# Peripherals.net
KiCad netlist of a schematic drawn in Altium Designer
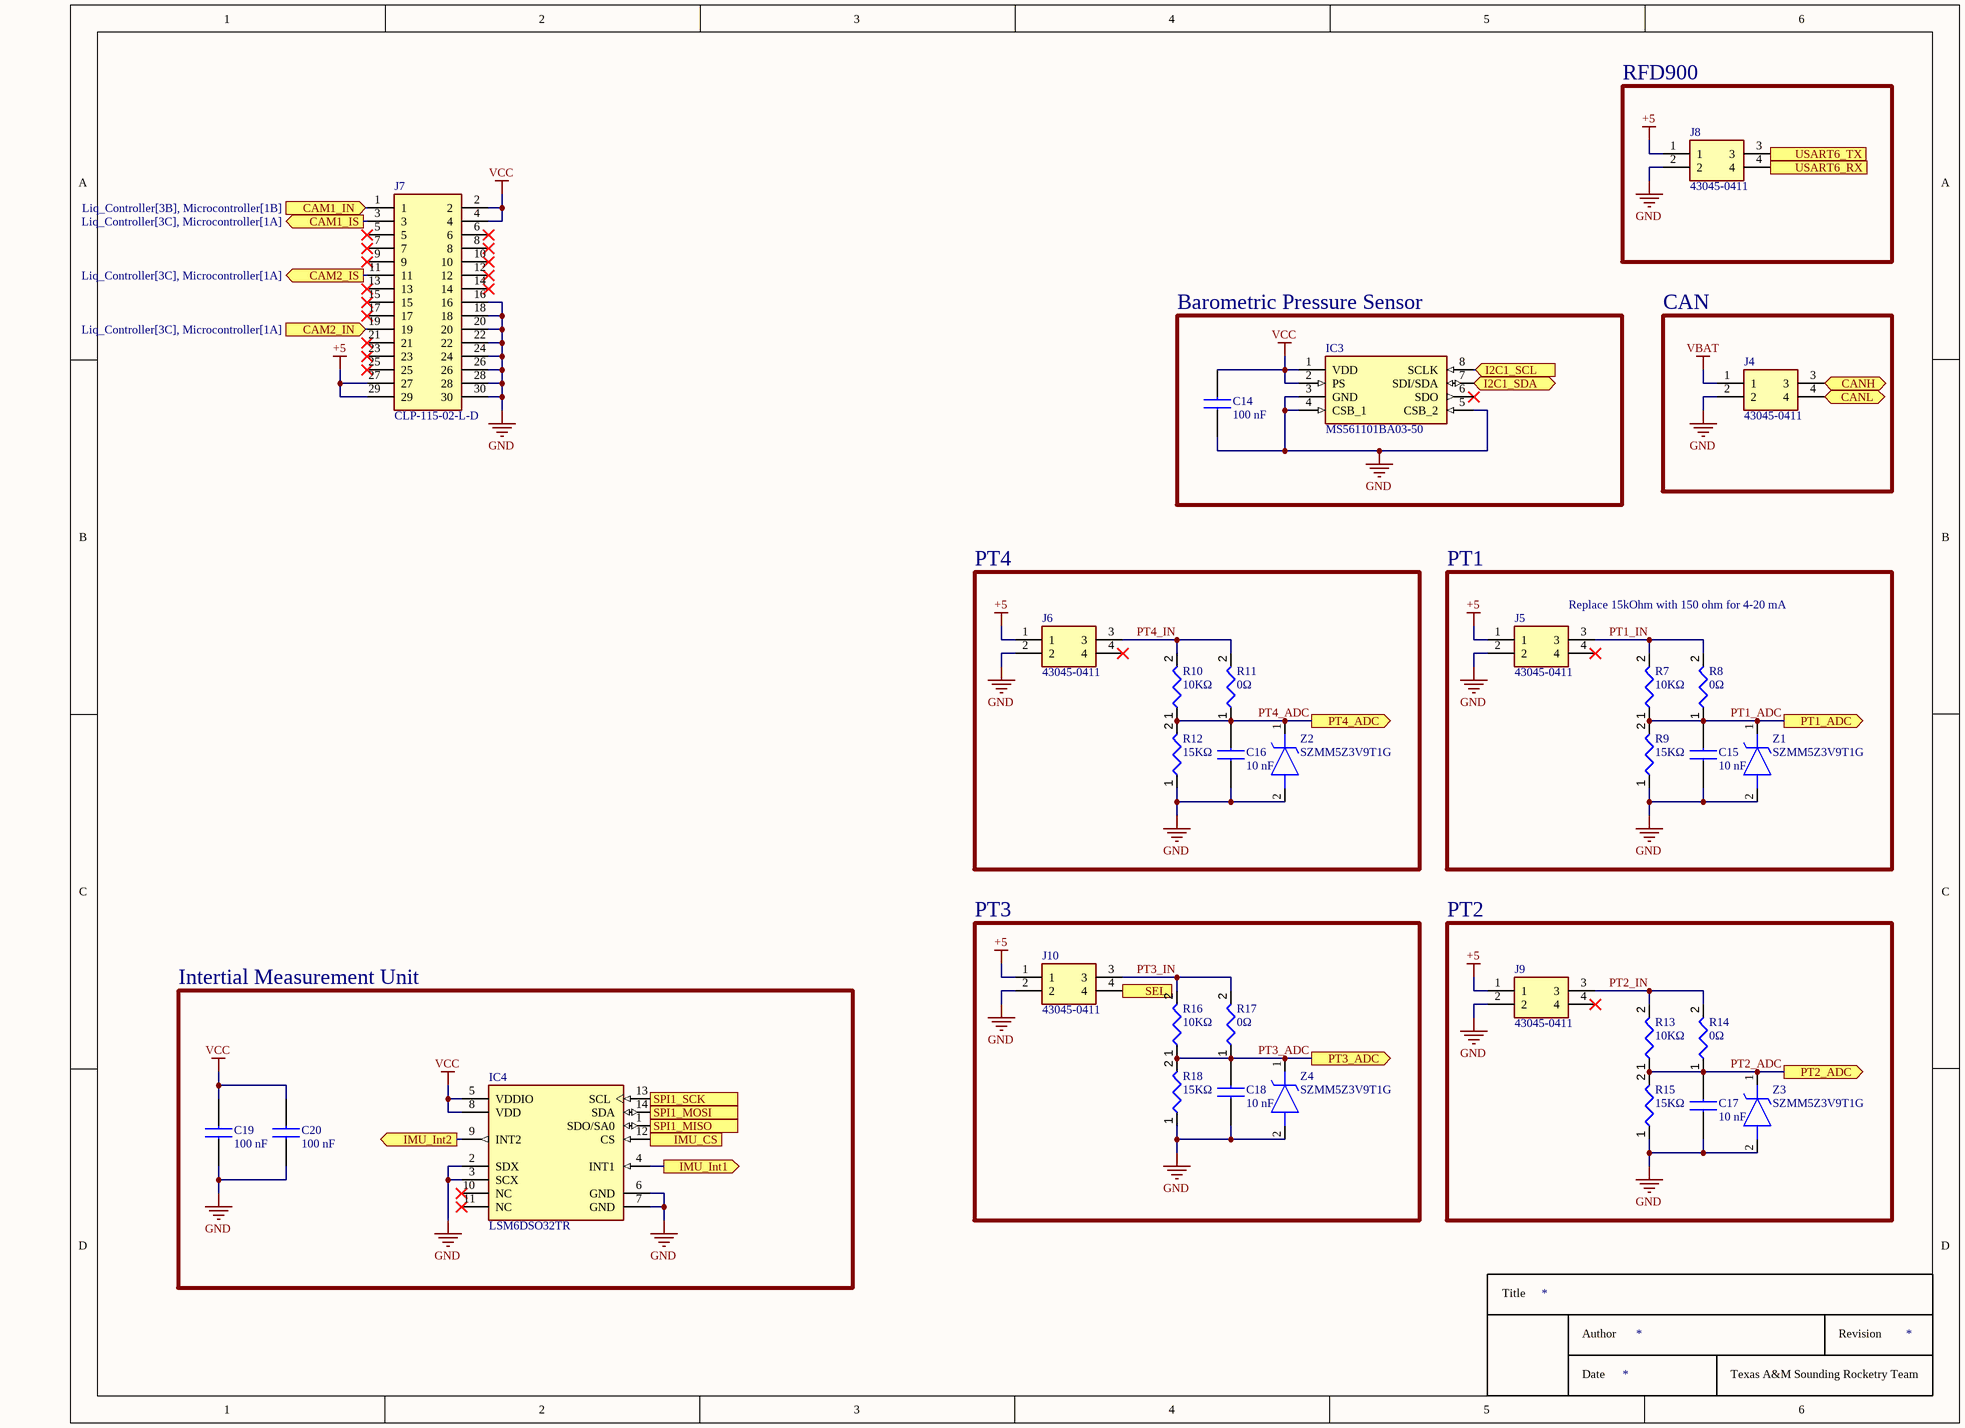
[diagram p0: Peripherals.SchDoc]

(export (version "E")
  (design (tool "Eeschema 10.0.6"))
  (components
    (comp (ref "C14")
      (value "100 nF")
      (footprint "CAP_0603")
      (fields (field (name "TOLERANCE") "5%") (field (name "VOLTAGE") "50 V"))
      (libsource (lib "Capacitors") (part "Capacitor_BASE"))
    )
    (comp (ref "C15")
      (value "10 nF")
      (footprint "CAP_0603")
      (fields
        (field (name "TOLERANCE") "5%")
        (field (name "VOLTAGE") "50 V")
        (field (name "MPN") "581-06035C103JAT4A")
      )
      (libsource (lib "Capacitors") (part "Capacitor_BASE"))
    )
    (comp (ref "C16")
      (value "10 nF")
      (footprint "CAP_0603")
      (fields
        (field (name "TOLERANCE") "5%")
        (field (name "VOLTAGE") "50 V")
        (field (name "MPN") "581-06035C103JAT4A")
      )
      (libsource (lib "Capacitors") (part "Capacitor_BASE"))
    )
    (comp (ref "C17")
      (value "10 nF")
      (footprint "CAP_0603")
      (fields
        (field (name "TOLERANCE") "5%")
        (field (name "VOLTAGE") "50 V")
        (field (name "MPN") "581-06035C103JAT4A")
      )
      (libsource (lib "Capacitors") (part "Capacitor_BASE"))
    )
    (comp (ref "C18")
      (value "10 nF")
      (footprint "CAP_0603")
      (fields
        (field (name "TOLERANCE") "5%")
        (field (name "VOLTAGE") "50 V")
        (field (name "MPN") "581-06035C103JAT4A")
      )
      (libsource (lib "Capacitors") (part "Capacitor_BASE"))
    )
    (comp (ref "C19")
      (value "100 nF")
      (footprint "CAP_0603")
      (fields
        (field (name "TOLERANCE") "5%")
        (field (name "VOLTAGE") "50 V")
        (field (name "MPN") "581-06035C104JAT2A")
      )
      (libsource (lib "Capacitors") (part "Capacitor_BASE"))
    )
    (comp (ref "C20")
      (value "100 nF")
      (footprint "CAP_0603")
      (fields
        (field (name "TOLERANCE") "5%")
        (field (name "VOLTAGE") "50 V")
        (field (name "MPN") "581-06035C104JAT2A")
      )
      (libsource (lib "Capacitors") (part "Capacitor_BASE"))
    )
    (comp (ref "IC3")
      (value "MS561101BA03-50")
      (footprint "Sensors:MS561101BA03-50")
      (description "Integrated Circuit")
      (fields (field (name "MPN") "824-MS561101BA03-50"))
      (libsource (lib "Sensors") (part "MS561101BA03-50"))
    )
    (comp (ref "IC4")
      (value "LSM6DSO32TR")
      (footprint "Sensors:XDCR_LSM6DSO32TR")
      (description "Accelerometer, Gyroscope, Temperature, 6 Axis Sensor IÂ²C, SPI Output")
      (fields (field (name "MF") "STMicroelectronics") (field (name "MPN") "511-LSM6DSO32TR"))
      (libsource (lib "Sensors") (part "LSM6DSO32TR"))
    )
    (comp (ref "J4")
      (value "43045-0411")
      (footprint "SamacSys:43045-04YY_09101192")
      (description "Connector")
      (fields (field (name "MOUSER PART NUMBER") "538-43045-0411"))
      (libsource (lib "*") (part "43045-0411"))
    )
    (comp (ref "J5")
      (value "43045-0411")
      (footprint "SamacSys:43045-04YY_09101192")
      (description "Connector")
      (fields (field (name "MOUSER PART NUMBER") "538-43045-0411"))
      (libsource (lib "*") (part "43045-0411"))
    )
    (comp (ref "J6")
      (value "43045-0411")
      (footprint "SamacSys:43045-04YY_09101192")
      (description "Connector")
      (fields (field (name "MOUSER PART NUMBER") "538-43045-0411"))
      (libsource (lib "*") (part "43045-0411"))
    )
    (comp (ref "J7")
      (value "CLP-115-02-L-D")
      (footprint "Connectors:CLP-115-02-XXX-D")
      (description "2x15 Board to Board")
      (fields (field (name "MOUSER PART NUMBER") "200-CLP11502LD"))
      (libsource (lib "Connectors") (part "CLP-115-02-L-D"))
    )
    (comp (ref "J8")
      (value "43045-0411")
      (footprint "SamacSys:43045-04YY_09101192")
      (description "Connector")
      (fields (field (name "MOUSER PART NUMBER") "538-43045-0411"))
      (libsource (lib "*") (part "43045-0411"))
    )
    (comp (ref "J9")
      (value "43045-0411")
      (footprint "SamacSys:43045-04YY_09101192")
      (description "Connector")
      (fields (field (name "MOUSER PART NUMBER") "538-43045-0411"))
      (libsource (lib "*") (part "43045-0411"))
    )
    (comp (ref "J10")
      (value "43045-0411")
      (footprint "SamacSys:43045-04YY_09101192")
      (description "Connector")
      (fields (field (name "MOUSER PART NUMBER") "538-43045-0411"))
      (libsource (lib "*") (part "43045-0411"))
    )
    (comp (ref "R7")
      (value "10KΩ")
      (footprint "RES_0603")
      (description "Thick Film Resistors - SMD General Purpose Chip Resistor 0603, 10kOhms, 1%, 1/10W")
      (fields (field (name "TOLERANCE") "0.01") (field (name "POWER") "0.1W"))
      (libsource (lib "Resistors") (part "Resistor_BASE"))
    )
    (comp (ref "R8")
      (value "0Ω")
      (footprint "RES_0603")
      (description "Thick Film Resistors - SMD General Purpose Chip Resistor 0603, 0Ohms, 1%, 1/10W")
      (fields (field (name "TOLERANCE") "0.01") (field (name "POWER") "0.1W"))
      (libsource (lib "Resistors") (part "Resistor_BASE"))
    )
    (comp (ref "R9")
      (value "15KΩ")
      (footprint "RES_0603")
      (description "Thick Film Resistors - SMD General Purpose Chip Resistor 0603, 15kOhms, 1%, 1/10W")
      (fields (field (name "TOLERANCE") "0.01") (field (name "POWER") "0.1W"))
      (libsource (lib "Resistors") (part "Resistor_BASE"))
    )
    (comp (ref "R10")
      (value "10KΩ")
      (footprint "RES_0603")
      (description "Thick Film Resistors - SMD General Purpose Chip Resistor 0603, 10kOhms, 1%, 1/10W")
      (fields (field (name "TOLERANCE") "0.01") (field (name "POWER") "0.1W"))
      (libsource (lib "Resistors") (part "Resistor_BASE"))
    )
    (comp (ref "R11")
      (value "0Ω")
      (footprint "RES_0603")
      (description "Thick Film Resistors - SMD General Purpose Chip Resistor 0603, 0Ohms, 1%, 1/10W")
      (fields (field (name "TOLERANCE") "0.01") (field (name "POWER") "0.1W"))
      (libsource (lib "Resistors") (part "Resistor_BASE"))
    )
    (comp (ref "R12")
      (value "15KΩ")
      (footprint "RES_0603")
      (description "Thick Film Resistors - SMD General Purpose Chip Resistor 0603, 15kOhms, 1%, 1/10W")
      (fields (field (name "TOLERANCE") "0.01") (field (name "POWER") "0.1W"))
      (libsource (lib "Resistors") (part "Resistor_BASE"))
    )
    (comp (ref "R13")
      (value "10KΩ")
      (footprint "RES_0603")
      (description "Thick Film Resistors - SMD General Purpose Chip Resistor 0603, 10kOhms, 1%, 1/10W")
      (fields (field (name "TOLERANCE") "0.01") (field (name "POWER") "0.1W"))
      (libsource (lib "Resistors") (part "Resistor_BASE"))
    )
    (comp (ref "R14")
      (value "0Ω")
      (footprint "RES_0603")
      (description "Thick Film Resistors - SMD General Purpose Chip Resistor 0603, 0Ohms, 1%, 1/10W")
      (fields (field (name "TOLERANCE") "0.01") (field (name "POWER") "0.1W"))
      (libsource (lib "Resistors") (part "Resistor_BASE"))
    )
    (comp (ref "R15")
      (value "15KΩ")
      (footprint "RES_0603")
      (description "Thick Film Resistors - SMD General Purpose Chip Resistor 0603, 15kOhms, 1%, 1/10W")
      (fields (field (name "TOLERANCE") "0.01") (field (name "POWER") "0.1W"))
      (libsource (lib "Resistors") (part "Resistor_BASE"))
    )
    (comp (ref "R16")
      (value "10KΩ")
      (footprint "RES_0603")
      (description "Thick Film Resistors - SMD General Purpose Chip Resistor 0603, 10kOhms, 1%, 1/10W")
      (fields (field (name "TOLERANCE") "0.01") (field (name "POWER") "0.1W"))
      (libsource (lib "Resistors") (part "Resistor_BASE"))
    )
    (comp (ref "R17")
      (value "0Ω")
      (footprint "RES_0603")
      (description "Thick Film Resistors - SMD General Purpose Chip Resistor 0603, 0Ohms, 1%, 1/10W")
      (fields (field (name "TOLERANCE") "0.01") (field (name "POWER") "0.1W"))
      (libsource (lib "Resistors") (part "Resistor_BASE"))
    )
    (comp (ref "R18")
      (value "15KΩ")
      (footprint "RES_0603")
      (description "Thick Film Resistors - SMD General Purpose Chip Resistor 0603, 15kOhms, 1%, 1/10W")
      (fields (field (name "TOLERANCE") "0.01") (field (name "POWER") "0.1W"))
      (libsource (lib "Resistors") (part "Resistor_BASE"))
    )
    (comp (ref "Z1")
      (value "SZMM5Z3V9T1G")
      (footprint "Diodes:SODFL1608X70N")
      (description "Zener Diode")
      (fields (field (name "MOUSER PART NUMBER") "863-SZMM5Z3V9T1G"))
      (libsource (lib "Diodes") (part "SZMM5Z3V9T1G"))
    )
    (comp (ref "Z2")
      (value "SZMM5Z3V9T1G")
      (footprint "Diodes:SODFL1608X70N")
      (description "Zener Diode")
      (fields (field (name "MOUSER PART NUMBER") "863-SZMM5Z3V9T1G"))
      (libsource (lib "Diodes") (part "SZMM5Z3V9T1G"))
    )
    (comp (ref "Z3")
      (value "SZMM5Z3V9T1G")
      (footprint "Diodes:SODFL1608X70N")
      (description "Zener Diode")
      (fields (field (name "MOUSER PART NUMBER") "863-SZMM5Z3V9T1G"))
      (libsource (lib "Diodes") (part "SZMM5Z3V9T1G"))
    )
    (comp (ref "Z4")
      (value "SZMM5Z3V9T1G")
      (footprint "Diodes:SODFL1608X70N")
      (description "Zener Diode")
      (fields (field (name "MOUSER PART NUMBER") "863-SZMM5Z3V9T1G"))
      (libsource (lib "Diodes") (part "SZMM5Z3V9T1G"))
    )
  )
  (nets
    (net (code "1") (name "+5") (class "Default")
      (node (ref "J10") (pin "1") (pinfunction "1_1") (pintype "passive"))
      (node (ref "J5") (pin "1") (pinfunction "1_1") (pintype "passive"))
      (node (ref "J6") (pin "1") (pinfunction "1_1") (pintype "passive"))
      (node (ref "J7") (pin "27") (pinfunction "27_27") (pintype "passive"))
      (node (ref "J7") (pin "29") (pinfunction "29_29") (pintype "passive"))
      (node (ref "J8") (pin "1") (pinfunction "1_1") (pintype "passive"))
      (node (ref "J9") (pin "1") (pinfunction "1_1") (pintype "passive"))
    )
    (net (code "2") (name "/CAM1_IN") (class "Default")
      (node (ref "J7") (pin "1") (pinfunction "1_1") (pintype "passive"))
    )
    (net (code "3") (name "/CAM1_IS") (class "Default")
      (node (ref "J7") (pin "3") (pinfunction "3_3") (pintype "passive"))
    )
    (net (code "4") (name "/CAM2_IN") (class "Default")
      (node (ref "J7") (pin "19") (pinfunction "19_19") (pintype "passive"))
    )
    (net (code "5") (name "/CAM2_IS") (class "Default")
      (node (ref "J7") (pin "11") (pinfunction "11_11") (pintype "passive"))
    )
    (net (code "6") (name "/CANH") (class "Default")
      (node (ref "J4") (pin "3") (pinfunction "3_3") (pintype "passive"))
    )
    (net (code "7") (name "/CANL") (class "Default")
      (node (ref "J4") (pin "4") (pinfunction "4_4") (pintype "passive"))
    )
    (net (code "8") (name "/I2C1_SCL") (class "Default")
      (node (ref "IC3") (pin "8") (pinfunction "SCLK_8") (pintype "input"))
    )
    (net (code "9") (name "/I2C1_SDA") (class "Default")
      (node (ref "IC3") (pin "7") (pinfunction "SDI/SDA_7") (pintype "bidirectional"))
    )
    (net (code "10") (name "/IMU_CS") (class "Default")
      (node (ref "IC4") (pin "12") (pinfunction "CS_12") (pintype "input"))
    )
    (net (code "11") (name "/IMU_Int1") (class "Default")
      (node (ref "IC4") (pin "4") (pinfunction "INT1_4") (pintype "input"))
    )
    (net (code "12") (name "/IMU_Int2") (class "Default")
      (node (ref "IC4") (pin "9") (pinfunction "INT2_9") (pintype "output"))
    )
    (net (code "13") (name "/PT1_ADC") (class "Default")
      (node (ref "C15") (pin "2") (pinfunction "2_2") (pintype "passive"))
      (node (ref "R7") (pin "1") (pinfunction "1_1") (pintype "passive"))
      (node (ref "R8") (pin "1") (pinfunction "1_1") (pintype "passive"))
      (node (ref "R9") (pin "2") (pinfunction "2_2") (pintype "passive"))
      (node (ref "Z1") (pin "1") (pinfunction "K_1") (pintype "passive"))
    )
    (net (code "14") (name "/PT1_IN") (class "Default")
      (node (ref "J5") (pin "3") (pinfunction "3_3") (pintype "passive"))
      (node (ref "R7") (pin "2") (pinfunction "2_2") (pintype "passive"))
      (node (ref "R8") (pin "2") (pinfunction "2_2") (pintype "passive"))
    )
    (net (code "15") (name "/PT2_ADC") (class "Default")
      (node (ref "C17") (pin "2") (pinfunction "2_2") (pintype "passive"))
      (node (ref "R13") (pin "1") (pinfunction "1_1") (pintype "passive"))
      (node (ref "R14") (pin "1") (pinfunction "1_1") (pintype "passive"))
      (node (ref "R15") (pin "2") (pinfunction "2_2") (pintype "passive"))
      (node (ref "Z3") (pin "1") (pinfunction "K_1") (pintype "passive"))
    )
    (net (code "16") (name "/PT2_IN") (class "Default")
      (node (ref "J9") (pin "3") (pinfunction "3_3") (pintype "passive"))
      (node (ref "R13") (pin "2") (pinfunction "2_2") (pintype "passive"))
      (node (ref "R14") (pin "2") (pinfunction "2_2") (pintype "passive"))
    )
    (net (code "17") (name "/PT3_ADC") (class "Default")
      (node (ref "C18") (pin "2") (pinfunction "2_2") (pintype "passive"))
      (node (ref "R16") (pin "1") (pinfunction "1_1") (pintype "passive"))
      (node (ref "R17") (pin "1") (pinfunction "1_1") (pintype "passive"))
      (node (ref "R18") (pin "2") (pinfunction "2_2") (pintype "passive"))
      (node (ref "Z4") (pin "1") (pinfunction "K_1") (pintype "passive"))
    )
    (net (code "18") (name "/PT3_IN") (class "Default")
      (node (ref "J10") (pin "3") (pinfunction "3_3") (pintype "passive"))
      (node (ref "R16") (pin "2") (pinfunction "2_2") (pintype "passive"))
      (node (ref "R17") (pin "2") (pinfunction "2_2") (pintype "passive"))
    )
    (net (code "19") (name "/PT4_ADC") (class "Default")
      (node (ref "C16") (pin "2") (pinfunction "2_2") (pintype "passive"))
      (node (ref "R10") (pin "1") (pinfunction "1_1") (pintype "passive"))
      (node (ref "R11") (pin "1") (pinfunction "1_1") (pintype "passive"))
      (node (ref "R12") (pin "2") (pinfunction "2_2") (pintype "passive"))
      (node (ref "Z2") (pin "1") (pinfunction "K_1") (pintype "passive"))
    )
    (net (code "20") (name "/PT4_IN") (class "Default")
      (node (ref "J6") (pin "3") (pinfunction "3_3") (pintype "passive"))
      (node (ref "R10") (pin "2") (pinfunction "2_2") (pintype "passive"))
      (node (ref "R11") (pin "2") (pinfunction "2_2") (pintype "passive"))
    )
    (net (code "21") (name "/SEL") (class "Default")
      (node (ref "J10") (pin "4") (pinfunction "4_4") (pintype "passive"))
    )
    (net (code "22") (name "/SPI1_MISO") (class "Default")
      (node (ref "IC4") (pin "1") (pinfunction "SDO/SA0_1") (pintype "bidirectional"))
    )
    (net (code "23") (name "/SPI1_MOSI") (class "Default")
      (node (ref "IC4") (pin "14") (pinfunction "SDA_14") (pintype "bidirectional"))
    )
    (net (code "24") (name "/SPI1_SCK") (class "Default")
      (node (ref "IC4") (pin "13") (pinfunction "SCL_13") (pintype "input"))
    )
    (net (code "25") (name "/USART6_RX") (class "Default")
      (node (ref "J8") (pin "4") (pinfunction "4_4") (pintype "passive"))
    )
    (net (code "26") (name "/USART6_TX") (class "Default")
      (node (ref "J8") (pin "3") (pinfunction "3_3") (pintype "passive"))
    )
    (net (code "27") (name "GND") (class "Default")
      (node (ref "C14") (pin "1") (pinfunction "1_1") (pintype "passive"))
      (node (ref "C15") (pin "1") (pinfunction "1_1") (pintype "passive"))
      (node (ref "C16") (pin "1") (pinfunction "1_1") (pintype "passive"))
      (node (ref "C17") (pin "1") (pinfunction "1_1") (pintype "passive"))
      (node (ref "C18") (pin "1") (pinfunction "1_1") (pintype "passive"))
      (node (ref "C19") (pin "1") (pinfunction "1_1") (pintype "passive"))
      (node (ref "C20") (pin "1") (pinfunction "1_1") (pintype "passive"))
      (node (ref "IC3") (pin "3") (pinfunction "GND_3") (pintype "power_in"))
      (node (ref "IC3") (pin "4") (pinfunction "CSB_1_4") (pintype "input"))
      (node (ref "IC3") (pin "5") (pinfunction "CSB_2_5") (pintype "input"))
      (node (ref "IC4") (pin "2") (pinfunction "SDX_2") (pintype "passive"))
      (node (ref "IC4") (pin "3") (pinfunction "SCX_3") (pintype "passive"))
      (node (ref "IC4") (pin "6") (pinfunction "GND_6") (pintype "power_in"))
      (node (ref "IC4") (pin "7") (pinfunction "GND_7") (pintype "power_in"))
      (node (ref "J10") (pin "2") (pinfunction "2_2") (pintype "passive"))
      (node (ref "J4") (pin "2") (pinfunction "2_2") (pintype "passive"))
      (node (ref "J5") (pin "2") (pinfunction "2_2") (pintype "passive"))
      (node (ref "J6") (pin "2") (pinfunction "2_2") (pintype "passive"))
      (node (ref "J7") (pin "16") (pinfunction "16_16") (pintype "passive"))
      (node (ref "J7") (pin "18") (pinfunction "18_18") (pintype "passive"))
      (node (ref "J7") (pin "20") (pinfunction "20_20") (pintype "passive"))
      (node (ref "J7") (pin "22") (pinfunction "22_22") (pintype "passive"))
      (node (ref "J7") (pin "24") (pinfunction "24_24") (pintype "passive"))
      (node (ref "J7") (pin "26") (pinfunction "26_26") (pintype "passive"))
      (node (ref "J7") (pin "28") (pinfunction "28_28") (pintype "passive"))
      (node (ref "J7") (pin "30") (pinfunction "30_30") (pintype "passive"))
      (node (ref "J8") (pin "2") (pinfunction "2_2") (pintype "passive"))
      (node (ref "J9") (pin "2") (pinfunction "2_2") (pintype "passive"))
      (node (ref "R12") (pin "1") (pinfunction "1_1") (pintype "passive"))
      (node (ref "R15") (pin "1") (pinfunction "1_1") (pintype "passive"))
      (node (ref "R18") (pin "1") (pinfunction "1_1") (pintype "passive"))
      (node (ref "R9") (pin "1") (pinfunction "1_1") (pintype "passive"))
      (node (ref "Z1") (pin "2") (pinfunction "A_2") (pintype "passive"))
      (node (ref "Z2") (pin "2") (pinfunction "A_2") (pintype "passive"))
      (node (ref "Z3") (pin "2") (pinfunction "A_2") (pintype "passive"))
      (node (ref "Z4") (pin "2") (pinfunction "A_2") (pintype "passive"))
    )
    (net (code "28") (name "VBAT") (class "Default")
      (node (ref "J4") (pin "1") (pinfunction "1_1") (pintype "passive"))
    )
    (net (code "29") (name "VCC") (class "Default")
      (node (ref "C14") (pin "2") (pinfunction "2_2") (pintype "passive"))
      (node (ref "C19") (pin "2") (pinfunction "2_2") (pintype "passive"))
      (node (ref "C20") (pin "2") (pinfunction "2_2") (pintype "passive"))
      (node (ref "IC3") (pin "1") (pinfunction "VDD_1") (pintype "power_in"))
      (node (ref "IC3") (pin "2") (pinfunction "PS_2") (pintype "input"))
      (node (ref "IC4") (pin "5") (pinfunction "VDDIO_5") (pintype "power_in"))
      (node (ref "IC4") (pin "8") (pinfunction "VDD_8") (pintype "power_in"))
      (node (ref "J7") (pin "2") (pinfunction "2_2") (pintype "passive"))
      (node (ref "J7") (pin "4") (pinfunction "4_4") (pintype "passive"))
    )
    (net (code "30") (name "unconnected-(IC3-SDO-Pad6)") (class "Default")
      (node (ref "IC3") (pin "6") (pinfunction "SDO_6") (pintype "output+no_connect"))
    )
    (net (code "31") (name "unconnected-(IC4-NC-Pad10)") (class "Default")
      (node (ref "IC4") (pin "10") (pinfunction "NC_10") (pintype "passive+no_connect"))
    )
    (net (code "32") (name "unconnected-(IC4-NC-Pad11)") (class "Default")
      (node (ref "IC4") (pin "11") (pinfunction "NC_11") (pintype "passive+no_connect"))
    )
    (net (code "33") (name "unconnected-(J5-Pad4)") (class "Default")
      (node (ref "J5") (pin "4") (pinfunction "4_4") (pintype "passive+no_connect"))
    )
    (net (code "34") (name "unconnected-(J6-Pad4)") (class "Default")
      (node (ref "J6") (pin "4") (pinfunction "4_4") (pintype "passive+no_connect"))
    )
    (net (code "35") (name "unconnected-(J7-Pad5)") (class "Default")
      (node (ref "J7") (pin "5") (pinfunction "5_5") (pintype "passive+no_connect"))
    )
    (net (code "36") (name "unconnected-(J7-Pad6)") (class "Default")
      (node (ref "J7") (pin "6") (pinfunction "6_6") (pintype "passive+no_connect"))
    )
    (net (code "37") (name "unconnected-(J7-Pad7)") (class "Default")
      (node (ref "J7") (pin "7") (pinfunction "7_7") (pintype "passive+no_connect"))
    )
    (net (code "38") (name "unconnected-(J7-Pad8)") (class "Default")
      (node (ref "J7") (pin "8") (pinfunction "8_8") (pintype "passive+no_connect"))
    )
    (net (code "39") (name "unconnected-(J7-Pad9)") (class "Default")
      (node (ref "J7") (pin "9") (pinfunction "9_9") (pintype "passive+no_connect"))
    )
    (net (code "40") (name "unconnected-(J7-Pad10)") (class "Default")
      (node (ref "J7") (pin "10") (pinfunction "10_10") (pintype "passive+no_connect"))
    )
    (net (code "41") (name "unconnected-(J7-Pad12)") (class "Default")
      (node (ref "J7") (pin "12") (pinfunction "12_12") (pintype "passive+no_connect"))
    )
    (net (code "42") (name "unconnected-(J7-Pad13)") (class "Default")
      (node (ref "J7") (pin "13") (pinfunction "13_13") (pintype "passive+no_connect"))
    )
    (net (code "43") (name "unconnected-(J7-Pad14)") (class "Default")
      (node (ref "J7") (pin "14") (pinfunction "14_14") (pintype "passive+no_connect"))
    )
    (net (code "44") (name "unconnected-(J7-Pad15)") (class "Default")
      (node (ref "J7") (pin "15") (pinfunction "15_15") (pintype "passive+no_connect"))
    )
    (net (code "45") (name "unconnected-(J7-Pad17)") (class "Default")
      (node (ref "J7") (pin "17") (pinfunction "17_17") (pintype "passive+no_connect"))
    )
    (net (code "46") (name "unconnected-(J7-Pad21)") (class "Default")
      (node (ref "J7") (pin "21") (pinfunction "21_21") (pintype "passive+no_connect"))
    )
    (net (code "47") (name "unconnected-(J7-Pad23)") (class "Default")
      (node (ref "J7") (pin "23") (pinfunction "23_23") (pintype "passive+no_connect"))
    )
    (net (code "48") (name "unconnected-(J7-Pad25)") (class "Default")
      (node (ref "J7") (pin "25") (pinfunction "25_25") (pintype "passive+no_connect"))
    )
    (net (code "49") (name "unconnected-(J9-Pad4)") (class "Default")
      (node (ref "J9") (pin "4") (pinfunction "4_4") (pintype "passive+no_connect"))
    )
  )
)
